# S06.net
KiCad netlist of a schematic drawn in Altium Designer
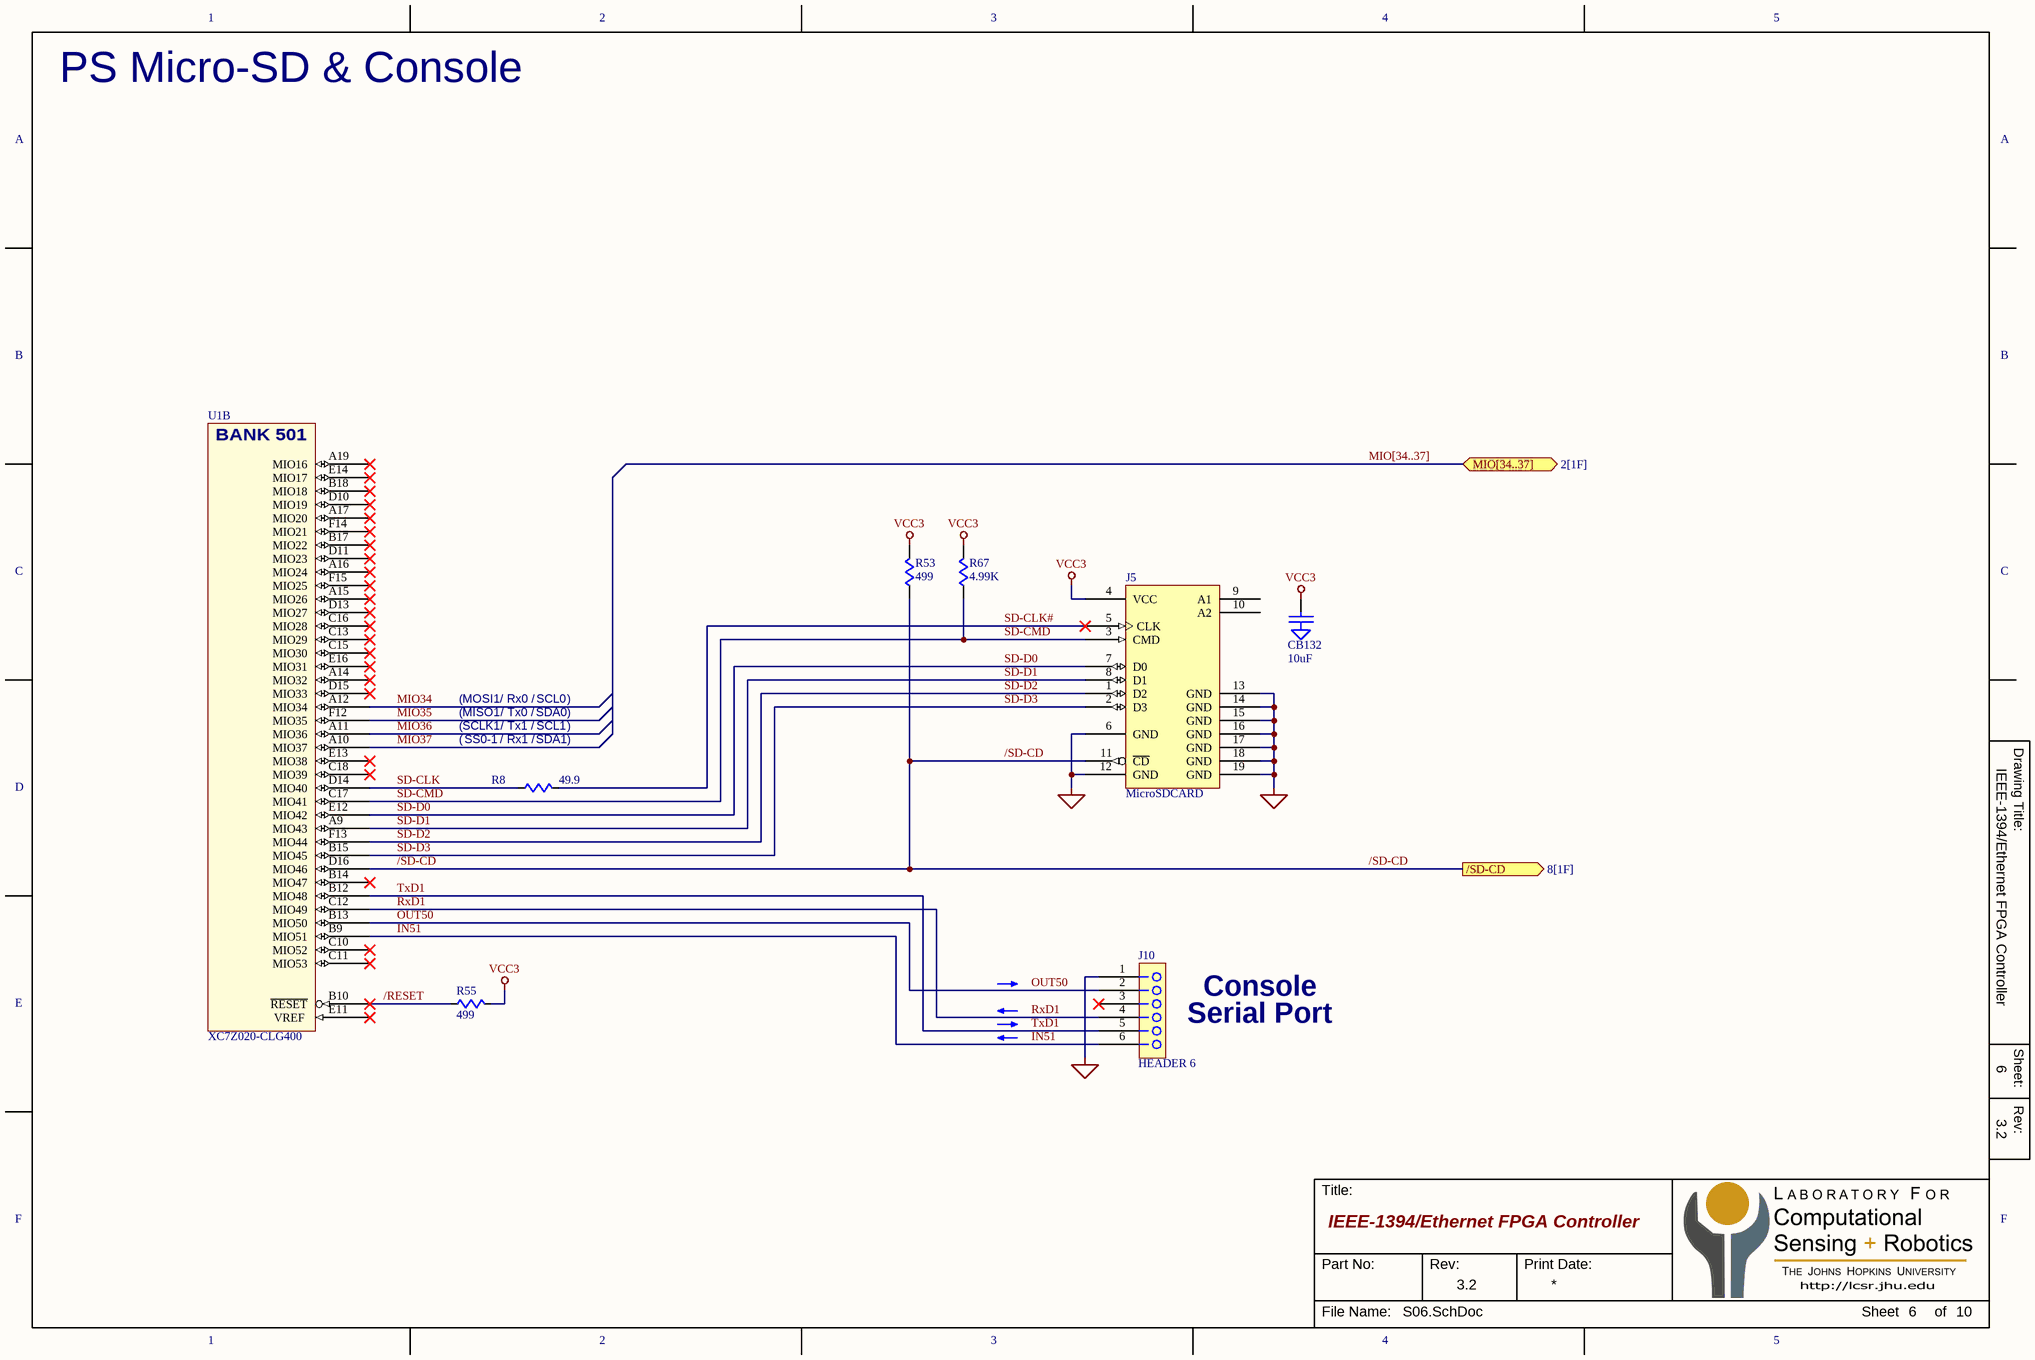
[diagram p0: S06.SchDoc]

(export (version "E")
  (design (tool "Eeschema 10.0.6"))
  (components
    (comp (ref "CB132") (value "10uF") (footprint "CB0603") (libsource (lib "LibJHU") (part "CAP-GND")))
    (comp (ref "J5")
      (value "MicroSDCARD")
      (footprint "CONN-uSD-JAE-ST12S0")
      (libsource (lib "LibJHU") (part "CONN-MICROSD-ST12S0"))
    )
    (comp (ref "J10")
      (value "HEADER 6")
      (footprint "HDR-6x1-100")
      (libsource (lib "LibJHU") (part "HEADER 6"))
    )
    (comp (ref "R8") (value "49.9") (footprint "R0201") (libsource (lib "LibJHU") (part "R")))
    (comp (ref "R53") (value "499") (footprint "R0402") (libsource (lib "") (part "R_1")))
    (comp (ref "R55") (value "499") (footprint "R0402") (libsource (lib "LibJHU") (part "R")))
    (comp (ref "R67") (value "4.99K") (footprint "R0402") (libsource (lib "") (part "R_1")))
    (comp (ref "U1")
      (value "XC7Z020-CLG400")
      (footprint "BGA-400-08mm")
      (libsource (lib "LibJHU") (part "XC7Z020-CLG400"))
    )
  )
  (nets
    (net (code "1") (name "/IN51") (class "Default")
      (node (ref "J10") (pin "6") (pinfunction "6_6") (pintype "passive"))
      (node (ref "U1") (pin "B9") (pinfunction "MIO51_B9") (pintype "bidirectional"))
    )
    (net (code "2") (name "/MIO34") (class "Default")
      (node (ref "U1") (pin "A12") (pinfunction "MIO34_A12") (pintype "bidirectional"))
    )
    (net (code "3") (name "/MIO35") (class "Default")
      (node (ref "U1") (pin "F12") (pinfunction "MIO35_F12") (pintype "bidirectional"))
    )
    (net (code "4") (name "/MIO36") (class "Default")
      (node (ref "U1") (pin "A11") (pinfunction "MIO36_A11") (pintype "bidirectional"))
    )
    (net (code "5") (name "/MIO37") (class "Default")
      (node (ref "U1") (pin "A10") (pinfunction "MIO37_A10") (pintype "bidirectional"))
    )
    (net (code "7") (name "/OUT50") (class "Default")
      (node (ref "J10") (pin "2") (pinfunction "2_2") (pintype "passive"))
      (node (ref "U1") (pin "B13") (pinfunction "MIO50_B13") (pintype "bidirectional"))
    )
    (net (code "8") (name "/RxD1") (class "Default")
      (node (ref "J10") (pin "4") (pinfunction "4_4") (pintype "passive"))
      (node (ref "U1") (pin "C12") (pinfunction "MIO49_C12") (pintype "bidirectional"))
    )
    (net (code "9") (name "/SD-CLK") (class "Default")
      (node (ref "R8") (pin "1") (pinfunction "1_1") (pintype "passive"))
      (node (ref "U1") (pin "D14") (pinfunction "MIO40_D14") (pintype "bidirectional"))
    )
    (net (code "10") (name "/SD-CLK#") (class "Default")
      (node (ref "J5") (pin "5") (pinfunction "CLK_5") (pintype "input"))
      (node (ref "R8") (pin "2") (pinfunction "2_2") (pintype "passive"))
    )
    (net (code "11") (name "/SD-CMD") (class "Default")
      (node (ref "J5") (pin "3") (pinfunction "CMD_3") (pintype "input"))
      (node (ref "R67") (pin "1") (pinfunction "1_1") (pintype "passive"))
      (node (ref "U1") (pin "C17") (pinfunction "MIO41_C17") (pintype "bidirectional"))
    )
    (net (code "12") (name "/SD-D0") (class "Default")
      (node (ref "J5") (pin "7") (pinfunction "D0_7") (pintype "bidirectional"))
      (node (ref "U1") (pin "E12") (pinfunction "MIO42_E12") (pintype "bidirectional"))
    )
    (net (code "13") (name "/SD-D1") (class "Default")
      (node (ref "J5") (pin "8") (pinfunction "D1_8") (pintype "bidirectional"))
      (node (ref "U1") (pin "A9") (pinfunction "MIO43_A9") (pintype "bidirectional"))
    )
    (net (code "14") (name "/SD-D2") (class "Default")
      (node (ref "J5") (pin "1") (pinfunction "D2_1") (pintype "bidirectional"))
      (node (ref "U1") (pin "F13") (pinfunction "MIO44_F13") (pintype "bidirectional"))
    )
    (net (code "15") (name "/SD-D3") (class "Default")
      (node (ref "J5") (pin "2") (pinfunction "D3_2") (pintype "bidirectional"))
      (node (ref "U1") (pin "B15") (pinfunction "MIO45_B15") (pintype "bidirectional"))
    )
    (net (code "16") (name "/TxD1") (class "Default")
      (node (ref "J10") (pin "5") (pinfunction "5_5") (pintype "passive"))
      (node (ref "U1") (pin "B12") (pinfunction "MIO48_B12") (pintype "bidirectional"))
    )
    (net (code "17") (name "/{slash}RESET") (class "Default")
      (node (ref "R55") (pin "1") (pinfunction "1_1") (pintype "passive"))
      (node (ref "U1") (pin "B10") (pinfunction "RESET_B10") (pintype "input"))
    )
    (net (code "18") (name "/{slash}SD-CD") (class "Default")
      (node (ref "J5") (pin "11") (pinfunction "CD_11") (pintype "output"))
      (node (ref "R53") (pin "1") (pinfunction "1_1") (pintype "passive"))
      (node (ref "U1") (pin "D16") (pinfunction "MIO46_D16") (pintype "bidirectional"))
    )
    (net (code "19") (name "GND") (class "Default")
      (node (ref "CB132") (pin "2") (pinfunction "GND_2") (pintype "power_in"))
      (node (ref "J10") (pin "1") (pinfunction "1_1") (pintype "passive"))
      (node (ref "J5") (pin "12") (pinfunction "GND_12") (pintype "power_in"))
      (node (ref "J5") (pin "13") (pinfunction "GND_13") (pintype "power_in"))
      (node (ref "J5") (pin "14") (pinfunction "GND_14") (pintype "power_in"))
      (node (ref "J5") (pin "15") (pinfunction "GND_15") (pintype "power_in"))
      (node (ref "J5") (pin "16") (pinfunction "GND_16") (pintype "power_in"))
      (node (ref "J5") (pin "17") (pinfunction "GND_17") (pintype "power_in"))
      (node (ref "J5") (pin "18") (pinfunction "GND_18") (pintype "power_in"))
      (node (ref "J5") (pin "19") (pinfunction "GND_19") (pintype "power_in"))
      (node (ref "J5") (pin "6") (pinfunction "GND_6") (pintype "power_in"))
    )
    (net (code "20") (name "VCC3") (class "Default")
      (node (ref "CB132") (pin "1") (pintype "passive"))
      (node (ref "J5") (pin "4") (pinfunction "VCC_4") (pintype "power_in"))
      (node (ref "R53") (pin "2") (pinfunction "2_2") (pintype "passive"))
      (node (ref "R55") (pin "2") (pinfunction "2_2") (pintype "passive"))
      (node (ref "R67") (pin "2") (pinfunction "2_2") (pintype "passive"))
    )
    (net (code "21") (name "unconnected-(J5-A1-Pad9)") (class "Default")
      (node (ref "J5") (pin "9") (pinfunction "A1_9") (pintype "passive"))
    )
    (net (code "22") (name "unconnected-(J5-A2-Pad10)") (class "Default")
      (node (ref "J5") (pin "10") (pinfunction "A2_10") (pintype "passive"))
    )
    (net (code "23") (name "unconnected-(J10-Pad3)") (class "Default")
      (node (ref "J10") (pin "3") (pinfunction "3_3") (pintype "passive+no_connect"))
    )
    (net (code "24") (name "unconnected-(U1B-MIO16-PadA19)") (class "Default")
      (node (ref "U1") (pin "A19") (pinfunction "MIO16_A19") (pintype "bidirectional+no_connect"))
    )
    (net (code "25") (name "unconnected-(U1B-MIO17-PadE14)") (class "Default")
      (node (ref "U1") (pin "E14") (pinfunction "MIO17_E14") (pintype "bidirectional+no_connect"))
    )
    (net (code "26") (name "unconnected-(U1B-MIO18-PadB18)") (class "Default")
      (node (ref "U1") (pin "B18") (pinfunction "MIO18_B18") (pintype "bidirectional+no_connect"))
    )
    (net (code "27") (name "unconnected-(U1B-MIO19-PadD10)") (class "Default")
      (node (ref "U1") (pin "D10") (pinfunction "MIO19_D10") (pintype "bidirectional+no_connect"))
    )
    (net (code "28") (name "unconnected-(U1B-MIO20-PadA17)") (class "Default")
      (node (ref "U1") (pin "A17") (pinfunction "MIO20_A17") (pintype "bidirectional+no_connect"))
    )
    (net (code "29") (name "unconnected-(U1B-MIO21-PadF14)") (class "Default")
      (node (ref "U1") (pin "F14") (pinfunction "MIO21_F14") (pintype "bidirectional+no_connect"))
    )
    (net (code "30") (name "unconnected-(U1B-MIO22-PadB17)") (class "Default")
      (node (ref "U1") (pin "B17") (pinfunction "MIO22_B17") (pintype "bidirectional+no_connect"))
    )
    (net (code "31") (name "unconnected-(U1B-MIO23-PadD11)") (class "Default")
      (node (ref "U1") (pin "D11") (pinfunction "MIO23_D11") (pintype "bidirectional+no_connect"))
    )
    (net (code "32") (name "unconnected-(U1B-MIO24-PadA16)") (class "Default")
      (node (ref "U1") (pin "A16") (pinfunction "MIO24_A16") (pintype "bidirectional+no_connect"))
    )
    (net (code "33") (name "unconnected-(U1B-MIO25-PadF15)") (class "Default")
      (node (ref "U1") (pin "F15") (pinfunction "MIO25_F15") (pintype "bidirectional+no_connect"))
    )
    (net (code "34") (name "unconnected-(U1B-MIO26-PadA15)") (class "Default")
      (node (ref "U1") (pin "A15") (pinfunction "MIO26_A15") (pintype "bidirectional+no_connect"))
    )
    (net (code "35") (name "unconnected-(U1B-MIO27-PadD13)") (class "Default")
      (node (ref "U1") (pin "D13") (pinfunction "MIO27_D13") (pintype "bidirectional+no_connect"))
    )
    (net (code "36") (name "unconnected-(U1B-MIO28-PadC16)") (class "Default")
      (node (ref "U1") (pin "C16") (pinfunction "MIO28_C16") (pintype "bidirectional+no_connect"))
    )
    (net (code "37") (name "unconnected-(U1B-MIO29-PadC13)") (class "Default")
      (node (ref "U1") (pin "C13") (pinfunction "MIO29_C13") (pintype "bidirectional+no_connect"))
    )
    (net (code "38") (name "unconnected-(U1B-MIO30-PadC15)") (class "Default")
      (node (ref "U1") (pin "C15") (pinfunction "MIO30_C15") (pintype "bidirectional+no_connect"))
    )
    (net (code "39") (name "unconnected-(U1B-MIO31-PadE16)") (class "Default")
      (node (ref "U1") (pin "E16") (pinfunction "MIO31_E16") (pintype "bidirectional+no_connect"))
    )
    (net (code "40") (name "unconnected-(U1B-MIO32-PadA14)") (class "Default")
      (node (ref "U1") (pin "A14") (pinfunction "MIO32_A14") (pintype "bidirectional+no_connect"))
    )
    (net (code "41") (name "unconnected-(U1B-MIO33-PadD15)") (class "Default")
      (node (ref "U1") (pin "D15") (pinfunction "MIO33_D15") (pintype "bidirectional+no_connect"))
    )
    (net (code "42") (name "unconnected-(U1B-MIO38-PadE13)") (class "Default")
      (node (ref "U1") (pin "E13") (pinfunction "MIO38_E13") (pintype "bidirectional+no_connect"))
    )
    (net (code "43") (name "unconnected-(U1B-MIO39-PadC18)") (class "Default")
      (node (ref "U1") (pin "C18") (pinfunction "MIO39_C18") (pintype "bidirectional+no_connect"))
    )
    (net (code "44") (name "unconnected-(U1B-MIO47-PadB14)") (class "Default")
      (node (ref "U1") (pin "B14") (pinfunction "MIO47_B14") (pintype "bidirectional+no_connect"))
    )
    (net (code "45") (name "unconnected-(U1B-MIO52-PadC10)") (class "Default")
      (node (ref "U1") (pin "C10") (pinfunction "MIO52_C10") (pintype "bidirectional+no_connect"))
    )
    (net (code "46") (name "unconnected-(U1B-MIO53-PadC11)") (class "Default")
      (node (ref "U1") (pin "C11") (pinfunction "MIO53_C11") (pintype "bidirectional+no_connect"))
    )
    (net (code "47") (name "unconnected-(U1B-VREF-PadE11)") (class "Default")
      (node (ref "U1") (pin "E11") (pinfunction "VREF_E11") (pintype "input+no_connect"))
    )
  )
)
